# ESP32_USB_C.net
KiCad netlist of a schematic drawn in Altium Designer
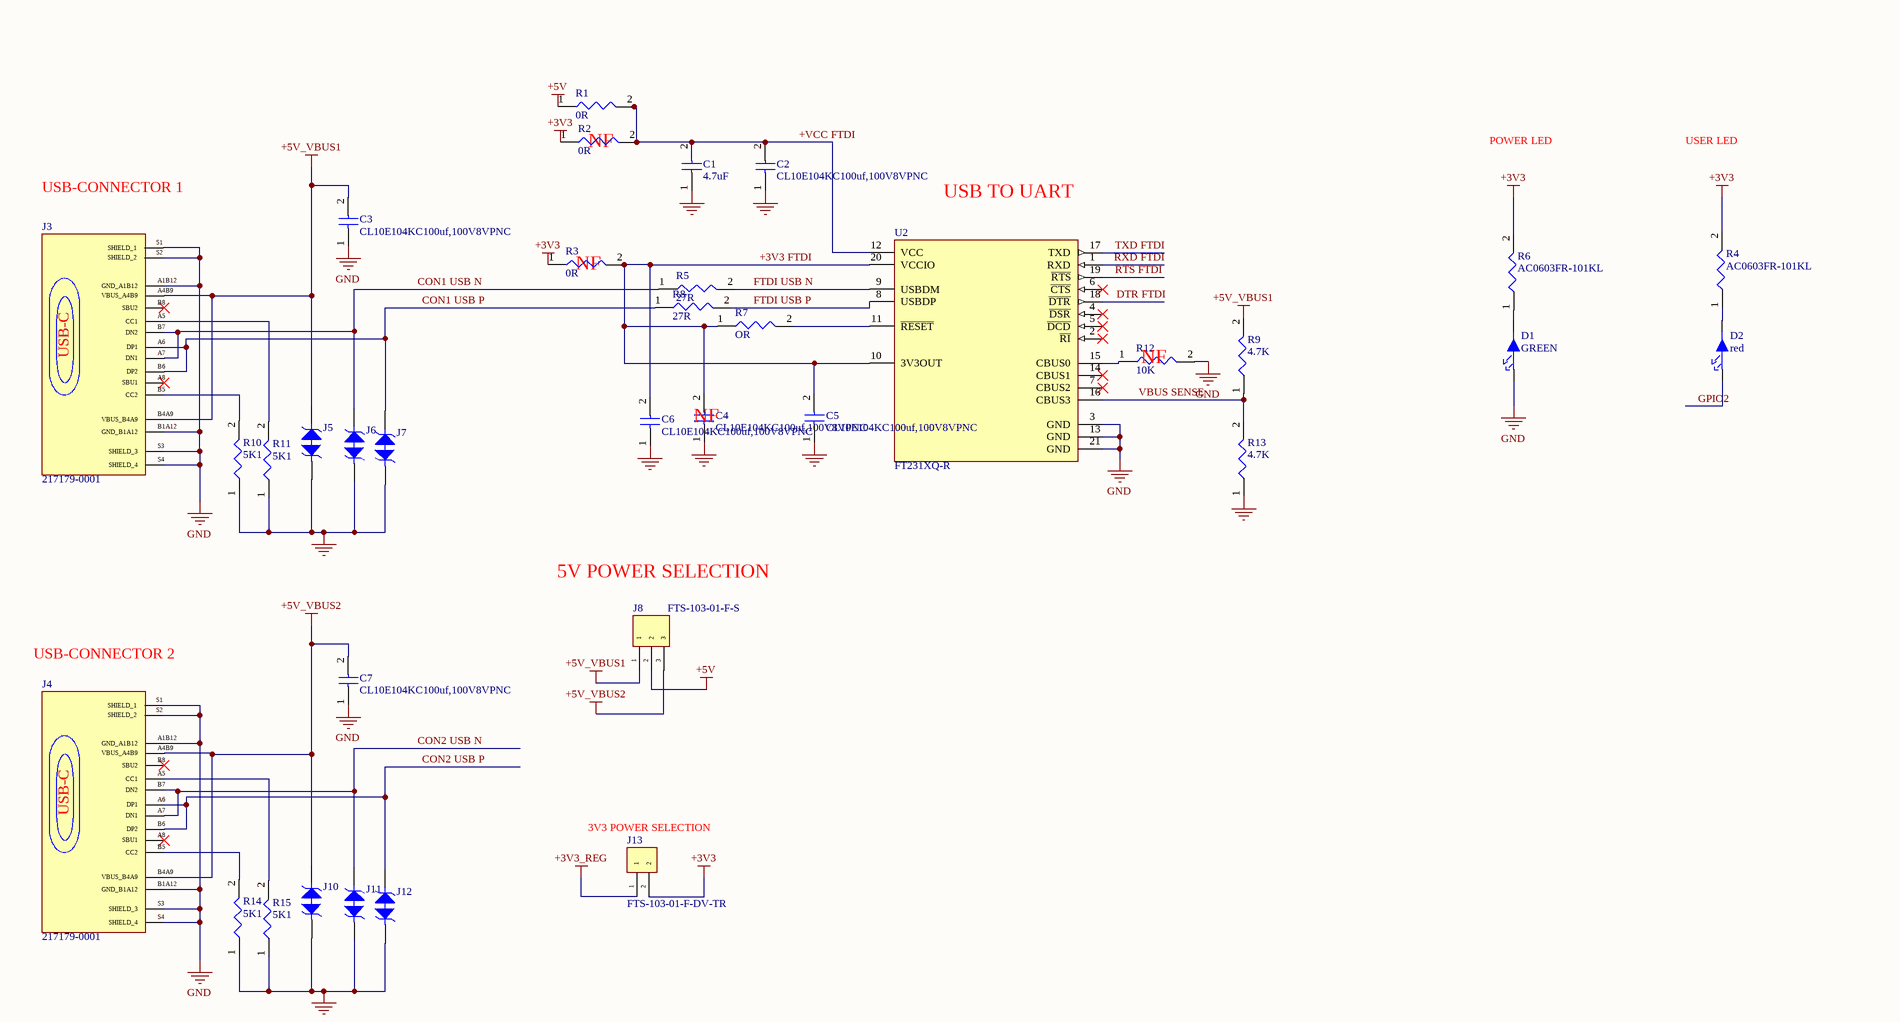
[diagram p0: ESP32_USB_C.SchDoc, top left]
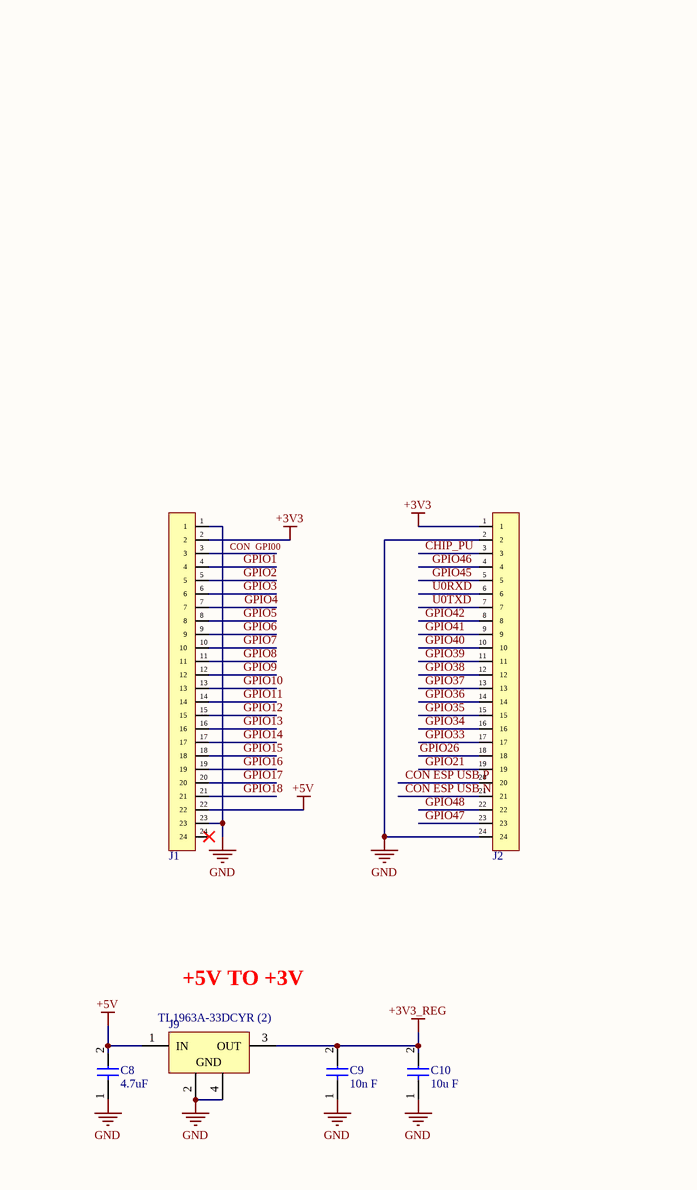
[diagram p1: ESP32_USB_C.SchDoc, top right]
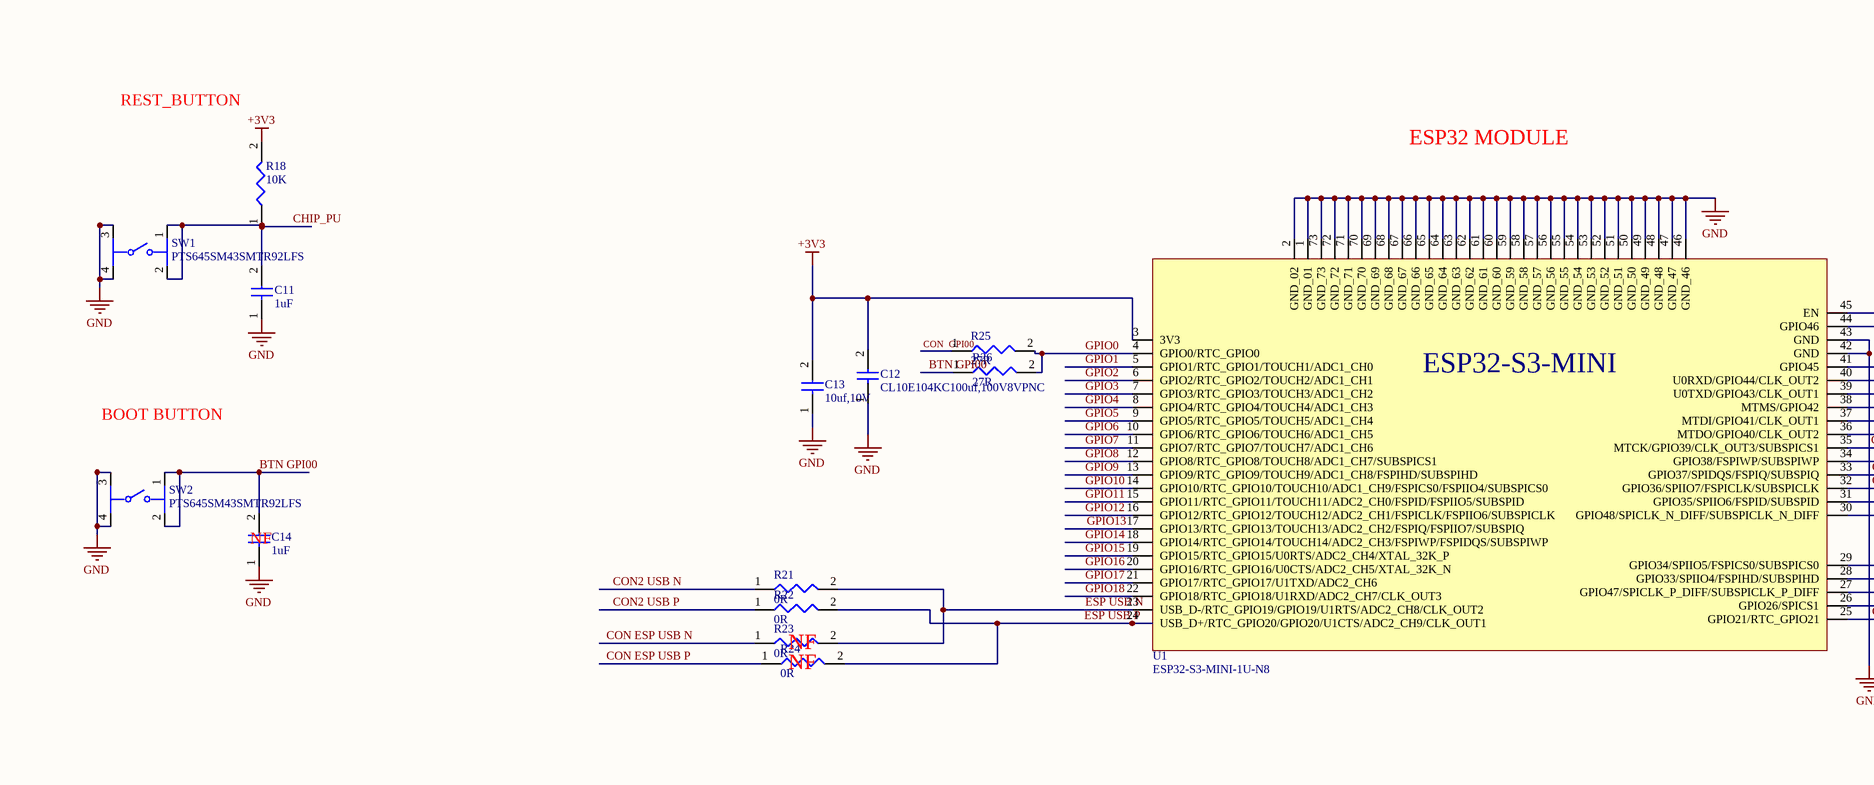
[diagram p2: ESP32_USB_C.SchDoc, bottom left]
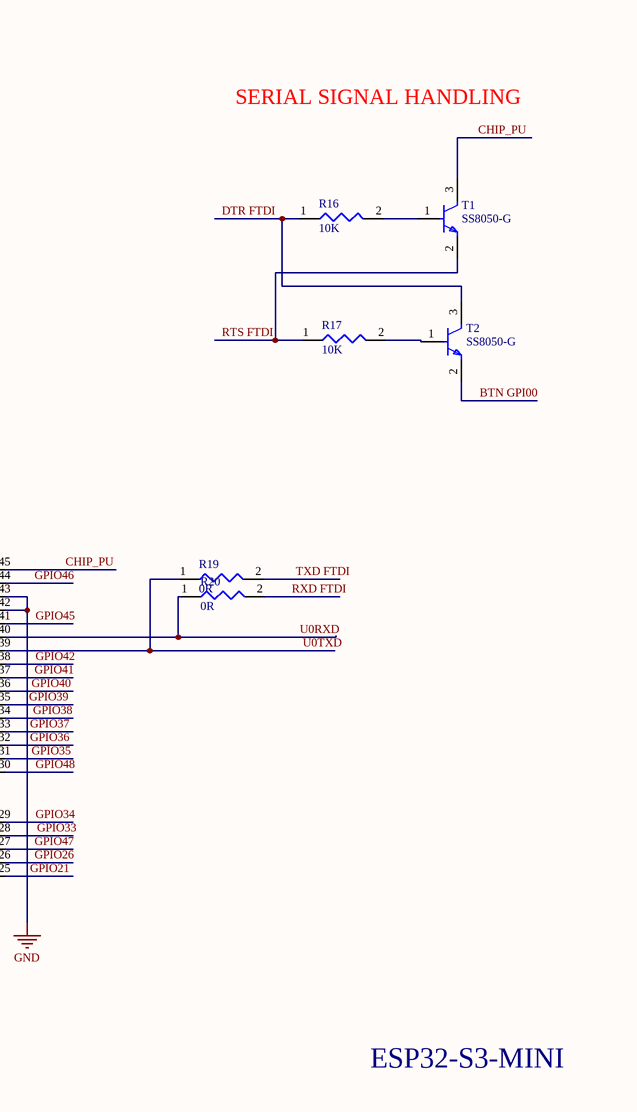
[diagram p3: ESP32_USB_C.SchDoc, bottom right]

(export (version "E")
  (design (tool "Eeschema 10.0.6"))
  (components
    (comp (ref "C1")
      (value "4.7uF")
      (footprint "CAPC1005X55N")
      (description "10V 4.7uF X5R ±20% 0402 Multilayer Ceramic Capacitors MLCC - SMD/SMT ROHS")
      (fields
        (field (name "MANUFACTURER") "Yageo Group")
        (field (name "MANUFACTURER PART NUMBER") "CC0402MRX5R6BB475")
      )
      (libsource (lib "ESP32_USB_C") (part "CC0402MRX5R6BB475"))
    )
    (comp (ref "C2")
      (value "CL10E104KC100uf,100V8VPNC")
      (footprint "CAPC1005X55N")
      (fields
        (field (name "MANUFACTURER") "Samsung Electro-Mechanics")
        (field (name "MANUFACTURER PART NUMBER") "CL10E104KC8VPNC")
      )
      (libsource (lib "ESP32_USB_C") (part "CL10E104KC8VPNC"))
    )
    (comp (ref "C3")
      (value "CL10E104KC100uf,100V8VPNC")
      (footprint "CAPC1005X55N")
      (fields
        (field (name "MANUFACTURER") "Samsung Electro-Mechanics")
        (field (name "MANUFACTURER PART NUMBER") "CL10E104KC8VPNC")
      )
      (libsource (lib "ESP32_USB_C") (part "CL10E104KC8VPNC"))
    )
    (comp (ref "C4")
      (value "CL10E104KC100uf,100V8VPNC")
      (footprint "CAPC1005X55N")
      (fields
        (field (name "MANUFACTURER") "Samsung Electro-Mechanics")
        (field (name "MANUFACTURER PART NUMBER") "CL10E104KC8VPNC")
      )
      (libsource (lib "ESP32_USB_C") (part "CL10E104KC8VPNC"))
    )
    (comp (ref "C5")
      (value "CL10E104KC100uf,100V8VPNC")
      (footprint "CAPC1005X55N")
      (fields
        (field (name "MANUFACTURER") "Samsung Electro-Mechanics")
        (field (name "MANUFACTURER PART NUMBER") "CL10E104KC8VPNC")
      )
      (libsource (lib "ESP32_USB_C") (part "CL10E104KC8VPNC"))
    )
    (comp (ref "C6")
      (value "CL10E104KC100uf,100V8VPNC")
      (footprint "CAPC1005X55N")
      (fields
        (field (name "MANUFACTURER") "Samsung Electro-Mechanics")
        (field (name "MANUFACTURER PART NUMBER") "CL10E104KC8VPNC")
      )
      (libsource (lib "ESP32_USB_C") (part "CL10E104KC8VPNC"))
    )
    (comp (ref "C7")
      (value "CL10E104KC100uf,100V8VPNC")
      (footprint "CAPC1005X55N")
      (fields
        (field (name "MANUFACTURER") "Samsung Electro-Mechanics")
        (field (name "MANUFACTURER PART NUMBER") "CL10E104KC8VPNC")
      )
      (libsource (lib "ESP32_USB_C") (part "CL10E104KC8VPNC"))
    )
    (comp (ref "C8")
      (value "4.7uF")
      (footprint "CAPC1005X55N")
      (description "10V 4.7uF X5R ±20% 0402 Multilayer Ceramic Capacitors MLCC - SMD/SMT ROHS")
      (fields
        (field (name "MANUFACTURER") "Yageo Group")
        (field (name "MANUFACTURER PART NUMBER") "CC0402MRX5R6BB475")
      )
      (libsource (lib "ESP32_USB_C") (part "CC0402MRX5R6BB475"))
    )
    (comp (ref "C9")
      (value "10n F")
      (footprint "CAPC1005X55N")
      (description "Surface Mount Ceramic Multilayer Capacitor Automotive Grade 0.01uF 20% X7R 50V 0612 Paper T/R")
      (fields
        (field (name "MANUFACTURER") "Yageo Group")
        (field (name "MANUFACTURER PART NUMBER") "AC0612MRX7R9BB103")
      )
      (libsource (lib "ESP32_USB_C") (part "AC0612MRX7R9BB103"))
    )
    (comp (ref "C10")
      (value "10u F")
      (footprint "CAPC1005X55N")
      (description "SMD Comm X7R 0805 (2012Metric) Ceramic Capacitor 0.079Lx0.049W 2.00mmx1.25mm X7R ±10% 10muF")
      (fields
        (field (name "MANUFACTURER") "Yageo Group")
        (field (name "MANUFACTURER PART NUMBER") "C0805C106K9RACTU")
      )
      (libsource (lib "ESP32_USB_C") (part "C0805C106K9RACTU"))
    )
    (comp (ref "C11")
      (value "1uF")
      (footprint "CAPC1005X55N")
      (description "16V 1uF X5R 卤10% 0402 Multilayer Ceramic Capacitors MLCC - SMD/SMT ROHS")
      (fields
        (field (name "MANUFACTURER") "Samsung Electro-Mechanics")
        (field (name "MANUFACTURER PART NUMBER") "CL05A105KO5NNNC")
      )
      (libsource (lib "ESP32_USB_C") (part "CL05A105KO5NNNC"))
    )
    (comp (ref "C12")
      (value "CL10E104KC100uf,100V8VPNC")
      (footprint "CAPC1005X55N")
      (fields
        (field (name "MANUFACTURER") "Samsung Electro-Mechanics")
        (field (name "MANUFACTURER PART NUMBER") "CL10E104KC8VPNC")
      )
      (libsource (lib "ESP32_USB_C") (part "CL10E104KC8VPNC"))
    )
    (comp (ref "C13")
      (value "10uf,10V")
      (footprint "CAPC1005X55N")
      (description "10V 10uF X5R 卤20% 0402 Multilayer Ceramic Capacitors MLCC - SMD/SMT ROHS")
      (fields
        (field (name "MANUFACTURER") "Samsung Electro-Mechanics")
        (field (name "MANUFACTURER PART NUMBER") "CL05A106MP8NUB8")
      )
      (libsource (lib "ESP32_USB_C") (part "CL05A106MP8NUB8"))
    )
    (comp (ref "C14")
      (value "1uF")
      (footprint "CAPC1005X55N")
      (description "16V 1uF X5R 卤10% 0402 Multilayer Ceramic Capacitors MLCC - SMD/SMT ROHS")
      (fields
        (field (name "MANUFACTURER") "Samsung Electro-Mechanics")
        (field (name "MANUFACTURER PART NUMBER") "CL05A105KO5NNNC")
      )
      (libsource (lib "ESP32_USB_C") (part "CL05A105KO5NNNC"))
    )
    (comp (ref "D1")
      (value "GREEN")
      (footprint "FP-APHCM2012CGCK-F01-MFG")
      (description "LED GREEN CLEAR CHIP SMD / Green 570nm LED Indication - Discrete 2.1V 0805 (2012 Metric)")
      (fields
        (field (name "MANUFACTURER") "Kingbright")
        (field (name "MANUFACTURER PART NUMBER") "APHCM2012CGCK-F01")
      )
      (libsource (lib "ESP32_USB_C") (part "APHCM2012CGCK-F01"))
    )
    (comp (ref "D2")
      (value "red")
      (footprint "LEDC2012X90N")
      (description "CML CMD17-21VRD/TR8 LED SMT 0805 2.0V 6mcd 140deg Red 3K Part of the VCC Family of Products")
      (fields (field (name "MANUFACTURER") "VCC") (field (name "MANUFACTURER PART NUMBER") "CMD17-21VRD/TR8"))
      (libsource (lib "ESP32_USB_C") (part "CMD17-21VRD/TR8"))
    )
    (comp (ref "J1")
      (value "22-28-4245")
      (footprint "7731111824LF")
      (description "Conn Unshrouded Header HDR 24 POS 2.54mm Solder ST Thru-Hole KK® Bag")
      (fields (field (name "MANUFACTURER") "Molex"))
      (libsource (lib "") (part "22-28-4245_1"))
    )
    (comp (ref "J2")
      (value "22-28-4245")
      (footprint "7731111824LF")
      (description "Conn Unshrouded Header HDR 24 POS 2.54mm Solder ST Thru-Hole KK® Bag")
      (fields (field (name "MANUFACTURER") "Molex"))
      (libsource (lib "ESP32_USB_C") (part "22-28-4245"))
    )
    (comp (ref "J3")
      (value "217179-0001")
      (footprint "FP-2171790001-MFG")
      (description "USB Connector, 16 Contact(s), Female, Right Angle, Surface Mount Terminal, Locking, Receptacle")
      (fields (field (name "MANUFACTURER") "Molex"))
      (libsource (lib "ESP32_USB_C") (part "217179-0001"))
    )
    (comp (ref "J4")
      (value "217179-0001")
      (footprint "FP-2171790001-MFG")
      (description "USB Connector, 16 Contact(s), Female, Right Angle, Surface Mount Terminal, Locking, Receptacle")
      (fields (field (name "MANUFACTURER") "Molex"))
      (libsource (lib "ESP32_USB_C") (part "217179-0001"))
    )
    (comp (ref "J5")
      (value "AQ3045-01ETG")
      (footprint "RTVS_SOD882_LTF-M")
      (description "TVS DIODE 12VC 3A SOD882 / ESD Suppressor TVS Bi-Dir 5.3V Automotive 2-Pin SOD-882 T/R")
      (fields (field (name "MANUFACTURER") "Littelfuse"))
      (libsource (lib "ESP32_USB_C") (part "AQ3045-01ETG"))
    )
    (comp (ref "J6")
      (value "AQ3045-01ETG")
      (footprint "RTVS_SOD882_LTF-M")
      (description "TVS DIODE 12VC 3A SOD882 / ESD Suppressor TVS Bi-Dir 5.3V Automotive 2-Pin SOD-882 T/R")
      (fields (field (name "MANUFACTURER") "Littelfuse"))
      (libsource (lib "ESP32_USB_C") (part "AQ3045-01ETG"))
    )
    (comp (ref "J7")
      (value "AQ3045-01ETG")
      (footprint "RTVS_SOD882_LTF-M")
      (description "TVS DIODE 12VC 3A SOD882 / ESD Suppressor TVS Bi-Dir 5.3V Automotive 2-Pin SOD-882 T/R")
      (fields (field (name "MANUFACTURER") "Littelfuse"))
      (libsource (lib "ESP32_USB_C") (part "AQ3045-01ETG"))
    )
    (comp (ref "J8")
      (value "FTS-103-01-F-S")
      (footprint "SAMTEC-FTS-103-01-X-S")
      (description "Pin Header, Board-to-Board, Wire-to-Board, 3.4 A, 1.27 mm, 1 Rows, 3 Contacts, Through Hole")
      (fields (field (name "MANUFACTURER") "Samtec"))
      (libsource (lib "ESP32_USB_C") (part "FTS-103-01-F-S"))
    )
    (comp (ref "J9")
      (value "TL1963A-33DCYR (2)")
      (footprint "DCY0004A_M")
      (description "1.5-A, 20-V, low-dropout voltage regulator with reverse current & reverse voltage protection")
      (fields
        (field (name "MANUFACTURER") "Texas Instruments")
        (field (name "MANUFACTURER PART NUMBER") "TL1963A-33DCYR")
      )
      (libsource (lib "ESP32_USB_C") (part "TL1963A-33DCYR (2)"))
    )
    (comp (ref "J10")
      (value "AQ3045-01ETG")
      (footprint "RTVS_SOD882_LTF-M")
      (description "TVS DIODE 12VC 3A SOD882 / ESD Suppressor TVS Bi-Dir 5.3V Automotive 2-Pin SOD-882 T/R")
      (fields (field (name "MANUFACTURER") "Littelfuse"))
      (libsource (lib "ESP32_USB_C") (part "AQ3045-01ETG"))
    )
    (comp (ref "J11")
      (value "AQ3045-01ETG")
      (footprint "RTVS_SOD882_LTF-M")
      (description "TVS DIODE 12VC 3A SOD882 / ESD Suppressor TVS Bi-Dir 5.3V Automotive 2-Pin SOD-882 T/R")
      (fields (field (name "MANUFACTURER") "Littelfuse"))
      (libsource (lib "ESP32_USB_C") (part "AQ3045-01ETG"))
    )
    (comp (ref "J12")
      (value "AQ3045-01ETG")
      (footprint "RTVS_SOD882_LTF-M")
      (description "TVS DIODE 12VC 3A SOD882 / ESD Suppressor TVS Bi-Dir 5.3V Automotive 2-Pin SOD-882 T/R")
      (fields (field (name "MANUFACTURER") "Littelfuse"))
      (libsource (lib "ESP32_USB_C") (part "AQ3045-01ETG"))
    )
    (comp (ref "J13")
      (value "FTS-103-01-F-DV-TR")
      (footprint "HDRV2W40P0X127_1X2_254X214X400P")
      (description "Pin Header, Board-to-Board, Wire-to-Board, 3.4 A, 1.27 mm, 2 Rows, 6 Contacts, Surface Mount")
      (fields (field (name "MANUFACTURER") "Samtec"))
      (libsource (lib "ESP32_USB_C") (part "FTS-103-01-F-DV-TR"))
    )
    (comp (ref "R1")
      (value "0R")
      (footprint "RESC1005X40N")
      (description "GENERAL PURPOSE CHIP RESISTOR Metal Glaze/thick Film, 0.0625W, 0ohm, Surface Mount, 0402")
      (fields
        (field (name "MANUFACTURER") "Yageo Group")
        (field (name "MANUFACTURER PART NUMBER") "RC0402JR-070RL")
      )
      (libsource (lib "ESP32_USB_C") (part "RC0402JR-070RL"))
    )
    (comp (ref "R2")
      (value "0R")
      (footprint "RESC1005X40N")
      (description "GENERAL PURPOSE CHIP RESISTOR Metal Glaze/thick Film, 0.0625W, 0ohm, Surface Mount, 0402")
      (fields
        (field (name "MANUFACTURER") "Yageo Group")
        (field (name "MANUFACTURER PART NUMBER") "RC0402JR-070RL")
      )
      (libsource (lib "ESP32_USB_C") (part "RC0402JR-070RL"))
    )
    (comp (ref "R3")
      (value "0R")
      (footprint "RESC1005X40N")
      (description "GENERAL PURPOSE CHIP RESISTOR Metal Glaze/thick Film, 0.0625W, 0ohm, Surface Mount, 0402")
      (fields
        (field (name "MANUFACTURER") "Yageo Group")
        (field (name "MANUFACTURER PART NUMBER") "RC0402JR-070RL")
      )
      (libsource (lib "ESP32_USB_C") (part "RC0402JR-070RL"))
    )
    (comp (ref "R4")
      (value "AC0603FR-101KL")
      (footprint "RESC1005X40N")
      (fields (field (name "MANUFACTURER") "Yageo Group") (field (name "TOLERANCE") "1%"))
      (libsource (lib "ESP32_USB_C") (part "AC0603FR-101KL"))
    )
    (comp (ref "R5")
      (value "27R")
      (footprint "RESC1005X40N")
      (description "62.5mW Thick Film Resistors 50V ±100ppm/℃ ±1% 27Ω 0402 Chip Resistor - Surface Mount ROHS")
      (fields
        (field (name "MANUFACTURER") "Yageo Group")
        (field (name "MANUFACTURER PART NUMBER") "RC0402FR-0727RL")
      )
      (libsource (lib "ESP32_USB_C") (part "RC0402FR-0727RL"))
    )
    (comp (ref "R6")
      (value "AC0603FR-101KL")
      (footprint "RESC1005X40N")
      (fields (field (name "MANUFACTURER") "Yageo Group") (field (name "TOLERANCE") "1%"))
      (libsource (lib "ESP32_USB_C") (part "AC0603FR-101KL"))
    )
    (comp (ref "R7")
      (value "OR")
      (footprint "RESC1005X40N")
      (description "Fixed Resistor, Thin Film, 0.063W, 1000ohm, 50V, 1% +/-Tol, 50ppm/Cel, Surface Mount, 0603")
      (fields
        (field (name "MANUFACTURER") "TE Connectivity")
        (field (name "MANUFACTURER PART NUMBER") "6-1879336-2")
      )
      (libsource (lib "ESP32_USB_C") (part "6-1879336-2"))
    )
    (comp (ref "R8")
      (value "27R")
      (footprint "RESC1005X40N")
      (description "62.5mW Thick Film Resistors 50V ±100ppm/℃ ±1% 27Ω 0402 Chip Resistor - Surface Mount ROHS")
      (fields
        (field (name "MANUFACTURER") "Yageo Group")
        (field (name "MANUFACTURER PART NUMBER") "RC0402FR-0727RL")
      )
      (libsource (lib "ESP32_USB_C") (part "RC0402FR-0727RL"))
    )
    (comp (ref "R9")
      (value "4.7K")
      (footprint "RESC1005X40N")
      (description "Res Thick Film 2512 4.7K Ohm 1% 1W ±100ppm/C Pad SMD T/R Automotive AEC-Q200")
      (fields
        (field (name "MANUFACTURER") "TE Connectivity")
        (field (name "MANUFACTURER PART NUMBER") "CRGCQ2512F4K7")
      )
      (libsource (lib "ESP32_USB_C") (part "CRGCQ2512F4K7"))
    )
    (comp (ref "R10")
      (value "5K1")
      (footprint "RESC1005X40N")
      (description "Res Thick Film 0402 5.1K Ohm 1% 0.1W(1/10W) ±100ppm/C Pad SMD Automotive T/R")
      (fields
        (field (name "MANUFACTURER") "Panasonic")
        (field (name "MANUFACTURER PART NUMBER") "ERJ2RKF5101X")
      )
      (libsource (lib "ESP32_USB_C") (part "ERJ2RKF5101X"))
    )
    (comp (ref "R11")
      (value "5K1")
      (footprint "RESC1005X40N")
      (description "Res Thick Film 0402 5.1K Ohm 1% 0.1W(1/10W) ±100ppm/C Pad SMD Automotive T/R")
      (fields
        (field (name "MANUFACTURER") "Panasonic")
        (field (name "MANUFACTURER PART NUMBER") "ERJ2RKF5101X")
      )
      (libsource (lib "ESP32_USB_C") (part "ERJ2RKF5101X"))
    )
    (comp (ref "R12")
      (value "10K")
      (footprint "RESC1005X40N")
      (description "Fixed Resistor, Metal Glaze/Thick Film, 0.2W, 10000ohm, 75V, 1% +/-Tol, Surface Mount, 0603")
      (fields
        (field (name "MANUFACTURER") "Yageo Group")
        (field (name "MANUFACTURER PART NUMBER") "AC0603FR-7W10KL")
      )
      (libsource (lib "ESP32_USB_C") (part "AC0603FR-7W10KL"))
    )
    (comp (ref "R13")
      (value "4.7K")
      (footprint "RESC1005X40N")
      (description "Res Thick Film 2512 4.7K Ohm 1% 1W ±100ppm/C Pad SMD T/R Automotive AEC-Q200")
      (fields
        (field (name "MANUFACTURER") "TE Connectivity")
        (field (name "MANUFACTURER PART NUMBER") "CRGCQ2512F4K7")
      )
      (libsource (lib "ESP32_USB_C") (part "CRGCQ2512F4K7"))
    )
    (comp (ref "R14")
      (value "5K1")
      (footprint "RESC1005X40N")
      (description "Res Thick Film 0402 5.1K Ohm 1% 0.1W(1/10W) ±100ppm/C Pad SMD Automotive T/R")
      (fields
        (field (name "MANUFACTURER") "Panasonic")
        (field (name "MANUFACTURER PART NUMBER") "ERJ2RKF5101X")
      )
      (libsource (lib "ESP32_USB_C") (part "ERJ2RKF5101X"))
    )
    (comp (ref "R15")
      (value "5K1")
      (footprint "RESC1005X40N")
      (description "Res Thick Film 0402 5.1K Ohm 1% 0.1W(1/10W) ±100ppm/C Pad SMD Automotive T/R")
      (fields
        (field (name "MANUFACTURER") "Panasonic")
        (field (name "MANUFACTURER PART NUMBER") "ERJ2RKF5101X")
      )
      (libsource (lib "ESP32_USB_C") (part "ERJ2RKF5101X"))
    )
    (comp (ref "R16")
      (value "10K")
      (footprint "RESC1005X40N")
      (description "Fixed Resistor, Metal Glaze/Thick Film, 0.2W, 10000ohm, 75V, 1% +/-Tol, Surface Mount, 0603")
      (fields
        (field (name "MANUFACTURER") "Yageo Group")
        (field (name "MANUFACTURER PART NUMBER") "AC0603FR-7W10KL")
      )
      (libsource (lib "ESP32_USB_C") (part "AC0603FR-7W10KL"))
    )
    (comp (ref "R17")
      (value "10K")
      (footprint "RESC1005X40N")
      (description "Fixed Resistor, Metal Glaze/Thick Film, 0.2W, 10000ohm, 75V, 1% +/-Tol, Surface Mount, 0603")
      (fields
        (field (name "MANUFACTURER") "Yageo Group")
        (field (name "MANUFACTURER PART NUMBER") "AC0603FR-7W10KL")
      )
      (libsource (lib "ESP32_USB_C") (part "AC0603FR-7W10KL"))
    )
    (comp (ref "R18")
      (value "10K")
      (footprint "RESC1005X40N")
      (description "Res Thick Film 0402 10K Ohm 1% 0.063W(1/16W) ±100ppm/°C Pad SMD T/R")
      (fields
        (field (name "MANUFACTURER") "Samsung Electro-Mechanics")
        (field (name "MANUFACTURER PART NUMBER") "RC1005F103CS")
      )
      (libsource (lib "ESP32_USB_C") (part "RC1005F103CS"))
    )
    (comp (ref "R19")
      (value "0R")
      (footprint "RESC1005X40N")
      (description "GENERAL PURPOSE CHIP RESISTOR Metal Glaze/thick Film, 0.0625W, 0ohm, Surface Mount, 0402")
      (fields
        (field (name "MANUFACTURER") "Yageo Group")
        (field (name "MANUFACTURER PART NUMBER") "RC0402JR-070RL")
      )
      (libsource (lib "ESP32_USB_C") (part "RC0402JR-070RL"))
    )
    (comp (ref "R20")
      (value "0R")
      (footprint "RESC1005X40N")
      (description "GENERAL PURPOSE CHIP RESISTOR Metal Glaze/thick Film, 0.0625W, 0ohm, Surface Mount, 0402")
      (fields
        (field (name "MANUFACTURER") "Yageo Group")
        (field (name "MANUFACTURER PART NUMBER") "RC0402JR-070RL")
      )
      (libsource (lib "ESP32_USB_C") (part "RC0402JR-070RL"))
    )
    (comp (ref "R21")
      (value "0R")
      (footprint "RESC1005X40N")
      (description "GENERAL PURPOSE CHIP RESISTOR Metal Glaze/thick Film, 0.0625W, 0ohm, Surface Mount, 0402")
      (fields
        (field (name "MANUFACTURER") "Yageo Group")
        (field (name "MANUFACTURER PART NUMBER") "RC0402JR-070RL")
      )
      (libsource (lib "ESP32_USB_C") (part "RC0402JR-070RL"))
    )
    (comp (ref "R22")
      (value "0R")
      (footprint "RESC1005X40N")
      (description "GENERAL PURPOSE CHIP RESISTOR Metal Glaze/thick Film, 0.0625W, 0ohm, Surface Mount, 0402")
      (fields
        (field (name "MANUFACTURER") "Yageo Group")
        (field (name "MANUFACTURER PART NUMBER") "RC0402JR-070RL")
      )
      (libsource (lib "ESP32_USB_C") (part "RC0402JR-070RL"))
    )
    (comp (ref "R23")
      (value "0R")
      (footprint "RESC1005X40N")
      (description "GENERAL PURPOSE CHIP RESISTOR Metal Glaze/thick Film, 0.0625W, 0ohm, Surface Mount, 0402")
      (fields
        (field (name "MANUFACTURER") "Yageo Group")
        (field (name "MANUFACTURER PART NUMBER") "RC0402JR-070RL")
      )
      (libsource (lib "ESP32_USB_C") (part "RC0402JR-070RL"))
    )
    (comp (ref "R24")
      (value "0R")
      (footprint "RESC1005X40N")
      (description "GENERAL PURPOSE CHIP RESISTOR Metal Glaze/thick Film, 0.0625W, 0ohm, Surface Mount, 0402")
      (fields
        (field (name "MANUFACTURER") "Yageo Group")
        (field (name "MANUFACTURER PART NUMBER") "RC0402JR-070RL")
      )
      (libsource (lib "ESP32_USB_C") (part "RC0402JR-070RL"))
    )
    (comp (ref "R25")
      (value "27R")
      (footprint "RESC1005X40N")
      (description "62.5mW Thick Film Resistors 50V ±100ppm/℃ ±1% 27Ω 0402 Chip Resistor - Surface Mount ROHS")
      (fields
        (field (name "MANUFACTURER") "Yageo Group")
        (field (name "MANUFACTURER PART NUMBER") "RC0402FR-0727RL")
      )
      (libsource (lib "ESP32_USB_C") (part "RC0402FR-0727RL"))
    )
    (comp (ref "R26")
      (value "27R")
      (footprint "RESC1005X40N")
      (description "62.5mW Thick Film Resistors 50V ±100ppm/℃ ±1% 27Ω 0402 Chip Resistor - Surface Mount ROHS")
      (fields
        (field (name "MANUFACTURER") "Yageo Group")
        (field (name "MANUFACTURER PART NUMBER") "RC0402FR-0727RL")
      )
      (libsource (lib "ESP32_USB_C") (part "RC0402FR-0727RL"))
    )
    (comp (ref "SW1")
      (value "PTS645SM43SMTR92LFS")
      (footprint "PTS645SM43SMTR92LFS_MFG")
      (description "Switch Tactile N.O SPST Round Button Gull Wing 0.05A 12VDC 100000Cycle 1.57N SMD T/R")
      (fields (field (name "MANUFACTURER") "C&K Components"))
      (libsource (lib "ESP32_USB_C") (part "PTS645SM43SMTR92LFS"))
    )
    (comp (ref "SW2")
      (value "PTS645SM43SMTR92LFS")
      (footprint "PTS645SM43SMTR92LFS_MFG")
      (description "Switch Tactile N.O SPST Round Button Gull Wing 0.05A 12VDC 100000Cycle 1.57N SMD T/R")
      (fields (field (name "MANUFACTURER") "C&K Components"))
      (libsource (lib "ESP32_USB_C") (part "PTS645SM43SMTR92LFS"))
    )
    (comp (ref "T1")
      (value "SS8050-G")
      (footprint "FP-SS8050-G-IPC_B")
      (fields (field (name "MANUFACTURER") "Comchip"))
      (libsource (lib "ESP32_USB_C") (part "SS8050-G"))
    )
    (comp (ref "T2")
      (value "SS8050-G")
      (footprint "FP-SS8050-G-IPC_B")
      (fields (field (name "MANUFACTURER") "Comchip"))
      (libsource (lib "ESP32_USB_C") (part "SS8050-G"))
    )
    (comp (ref "U1")
      (value "ESP32-S3-MINI-1U-N8")
      (footprint "XCVR_ESP32-S3-MINI-1U-N8")
      (description "WiFi-Module 802.11 2, 4GHz 150Mb/s")
      (fields (field (name "MANUFACTURER") "Espressif Systems"))
      (libsource (lib "ESP32_USB_C") (part "ESP32-S3-MINI-1U-N8"))
    )
    (comp (ref "U2")
      (value "FT231XQ-R")
      (footprint "FP-QFN-20-IPC_B")
      (libsource (lib "ESP32_USB_C") (part "FT231XQ-R Tape & Reel (TR) 2006 UART USB 2.0 interface controller 3.3V~5V 4mm 8mA 12Mbps UART Interface ICs Tape & Reel (TR) 2006 UART USB 2.0 interface controller 3.3V~5V 4mm 8mA 12Mbps"))
    )
  )
  (nets
    (net (code "1") (name "+3V3") (class "Default")
      (node (ref "C12") (pin "2") (pinfunction "2_2") (pintype "passive"))
      (node (ref "C13") (pin "2") (pinfunction "2_2") (pintype "passive"))
      (node (ref "J1") (pin "2") (pinfunction "2_2") (pintype "passive"))
      (node (ref "J13") (pin "2") (pinfunction "2_2") (pintype "passive"))
      (node (ref "J2") (pin "1") (pinfunction "1_1") (pintype "passive"))
      (node (ref "R18") (pin "2") (pinfunction "2_2") (pintype "passive"))
      (node (ref "R2") (pin "1") (pinfunction "1_1") (pintype "passive"))
      (node (ref "R3") (pin "1") (pinfunction "1_1") (pintype "passive"))
      (node (ref "R4") (pin "2") (pinfunction "2_2") (pintype "passive"))
      (node (ref "R6") (pin "2") (pinfunction "2_2") (pintype "passive"))
      (node (ref "U1") (pin "3") (pinfunction "3V3_3") (pintype "passive"))
    )
    (net (code "2") (name "+3V3_REG") (class "Default")
      (node (ref "C10") (pin "2") (pinfunction "2_2") (pintype "passive"))
      (node (ref "C9") (pin "2") (pinfunction "2_2") (pintype "passive"))
      (node (ref "J13") (pin "1") (pinfunction "1_1") (pintype "passive"))
      (node (ref "J9") (pin "3") (pinfunction "OUT_3") (pintype "power_in"))
    )
    (net (code "3") (name "+5V") (class "Default")
      (node (ref "C8") (pin "2") (pinfunction "2_2") (pintype "passive"))
      (node (ref "J1") (pin "22") (pinfunction "22_22") (pintype "passive"))
      (node (ref "J8") (pin "2") (pinfunction "2_2") (pintype "passive"))
      (node (ref "J9") (pin "1") (pinfunction "IN_1") (pintype "power_in"))
      (node (ref "R1") (pin "1") (pinfunction "1_1") (pintype "passive"))
    )
    (net (code "4") (name "+5V_VBUS1") (class "Default")
      (node (ref "C3") (pin "2") (pinfunction "2_2") (pintype "passive"))
      (node (ref "J3") (pin "A4B9") (pinfunction "VBUS_A4B9_A4B9") (pintype "passive"))
      (node (ref "J3") (pin "B4A9") (pinfunction "VBUS_B4A9_B4A9") (pintype "passive"))
      (node (ref "J5") (pin "2") (pintype "passive"))
      (node (ref "J8") (pin "1") (pinfunction "1_1") (pintype "passive"))
      (node (ref "R9") (pin "2") (pinfunction "2_2") (pintype "passive"))
    )
    (net (code "5") (name "+5V_VBUS2") (class "Default")
      (node (ref "C7") (pin "2") (pinfunction "2_2") (pintype "passive"))
      (node (ref "J10") (pin "2") (pintype "passive"))
      (node (ref "J4") (pin "A4B9") (pinfunction "VBUS_A4B9_A4B9") (pintype "passive"))
      (node (ref "J4") (pin "B4A9") (pinfunction "VBUS_B4A9_B4A9") (pintype "passive"))
      (node (ref "J8") (pin "3") (pinfunction "3_3") (pintype "passive"))
    )
    (net (code "6") (name "/+3V3 FTDI") (class "Default")
      (node (ref "C4") (pin "2") (pinfunction "2_2") (pintype "passive"))
      (node (ref "C5") (pin "2") (pinfunction "2_2") (pintype "passive"))
      (node (ref "C6") (pin "2") (pinfunction "2_2") (pintype "passive"))
      (node (ref "R3") (pin "2") (pinfunction "2_2") (pintype "passive"))
      (node (ref "R7") (pin "1") (pinfunction "1_1") (pintype "passive"))
      (node (ref "U2") (pin "10") (pinfunction "3V3OUT_10") (pintype "passive"))
      (node (ref "U2") (pin "20") (pinfunction "VCCIO_20") (pintype "passive"))
    )
    (net (code "7") (name "/+VCC FTDI") (class "Default")
      (node (ref "C1") (pin "2") (pinfunction "2_2") (pintype "passive"))
      (node (ref "C2") (pin "2") (pinfunction "2_2") (pintype "passive"))
      (node (ref "R1") (pin "2") (pinfunction "2_2") (pintype "passive"))
      (node (ref "R2") (pin "2") (pinfunction "2_2") (pintype "passive"))
      (node (ref "U2") (pin "12") (pinfunction "VCC_12") (pintype "passive"))
    )
    (net (code "8") (name "/BTN GPI00") (class "Default")
      (node (ref "C14") (pin "2") (pinfunction "2_2") (pintype "passive"))
      (node (ref "R26") (pin "1") (pinfunction "1_1") (pintype "passive"))
      (node (ref "SW2") (pin "1") (pinfunction "1_1") (pintype "passive"))
      (node (ref "SW2") (pin "2") (pinfunction "2_2") (pintype "passive"))
      (node (ref "T2") (pin "2") (pinfunction "E_2") (pintype "passive"))
    )
    (net (code "9") (name "/CHIP_PU") (class "Default")
      (node (ref "C11") (pin "2") (pinfunction "2_2") (pintype "passive"))
      (node (ref "J2") (pin "3") (pinfunction "3_3") (pintype "passive"))
      (node (ref "R18") (pin "1") (pinfunction "1_1") (pintype "passive"))
      (node (ref "SW1") (pin "1") (pinfunction "1_1") (pintype "passive"))
      (node (ref "SW1") (pin "2") (pinfunction "2_2") (pintype "passive"))
      (node (ref "T1") (pin "3") (pinfunction "C_3") (pintype "passive"))
      (node (ref "U1") (pin "45") (pinfunction "EN_45") (pintype "passive"))
    )
    (net (code "10") (name "/CON  GPI00") (class "Default")
      (node (ref "J1") (pin "3") (pinfunction "3_3") (pintype "passive"))
      (node (ref "R25") (pin "1") (pinfunction "1_1") (pintype "passive"))
    )
    (net (code "11") (name "/CON ESP USB N") (class "Default")
      (node (ref "J2") (pin "21") (pinfunction "21_21") (pintype "passive"))
      (node (ref "R23") (pin "1") (pinfunction "1_1") (pintype "passive"))
    )
    (net (code "12") (name "/CON ESP USB P") (class "Default")
      (node (ref "J2") (pin "20") (pinfunction "20_20") (pintype "passive"))
      (node (ref "R24") (pin "1") (pinfunction "1_1") (pintype "passive"))
    )
    (net (code "13") (name "/CON1 USB N") (class "Default")
      (node (ref "J3") (pin "A7") (pinfunction "DN1_A7") (pintype "passive"))
      (node (ref "J3") (pin "B7") (pinfunction "DN2_B7") (pintype "passive"))
      (node (ref "J6") (pin "2") (pintype "passive"))
      (node (ref "R5") (pin "1") (pinfunction "1_1") (pintype "passive"))
    )
    (net (code "14") (name "/CON1 USB P") (class "Default")
      (node (ref "J3") (pin "A6") (pinfunction "DP1_A6") (pintype "passive"))
      (node (ref "J3") (pin "B6") (pinfunction "DP2_B6") (pintype "passive"))
      (node (ref "J7") (pin "2") (pintype "passive"))
      (node (ref "R8") (pin "1") (pinfunction "1_1") (pintype "passive"))
    )
    (net (code "15") (name "/CON2 USB N") (class "Default")
      (node (ref "J11") (pin "2") (pintype "passive"))
      (node (ref "J4") (pin "A7") (pinfunction "DN1_A7") (pintype "passive"))
      (node (ref "J4") (pin "B7") (pinfunction "DN2_B7") (pintype "passive"))
      (node (ref "R21") (pin "1") (pinfunction "1_1") (pintype "passive"))
    )
    (net (code "16") (name "/CON2 USB P") (class "Default")
      (node (ref "J12") (pin "2") (pintype "passive"))
      (node (ref "J4") (pin "A6") (pinfunction "DP1_A6") (pintype "passive"))
      (node (ref "J4") (pin "B6") (pinfunction "DP2_B6") (pintype "passive"))
      (node (ref "R22") (pin "1") (pinfunction "1_1") (pintype "passive"))
    )
    (net (code "17") (name "/DTR FTDI") (class "Default")
      (node (ref "R16") (pin "1") (pinfunction "1_1") (pintype "passive"))
      (node (ref "T2") (pin "3") (pinfunction "C_3") (pintype "passive"))
      (node (ref "U2") (pin "18") (pinfunction "~{DTR}_18") (pintype "output"))
    )
    (net (code "18") (name "/ESP USB N") (class "Default")
      (node (ref "R21") (pin "2") (pinfunction "2_2") (pintype "passive"))
      (node (ref "R23") (pin "2") (pinfunction "2_2") (pintype "passive"))
      (node (ref "U1") (pin "23") (pinfunction "USB_D-/RTC_GPIO19/GPIO19/U1RTS/ADC2_CH8/CLK_OUT2_23") (pintype "passive"))
    )
    (net (code "19") (name "/ESP USB P") (class "Default")
      (node (ref "R22") (pin "2") (pinfunction "2_2") (pintype "passive"))
      (node (ref "R24") (pin "2") (pinfunction "2_2") (pintype "passive"))
      (node (ref "U1") (pin "24") (pinfunction "USB_D+/RTC_GPIO20/GPIO20/U1CTS/ADC2_CH9/CLK_OUT1_24") (pintype "passive"))
    )
    (net (code "20") (name "/FTDI USB N") (class "Default")
      (node (ref "R5") (pin "2") (pinfunction "2_2") (pintype "passive"))
      (node (ref "U2") (pin "9") (pinfunction "USBDM_9") (pintype "passive"))
    )
    (net (code "21") (name "/FTDI USB P") (class "Default")
      (node (ref "R8") (pin "2") (pinfunction "2_2") (pintype "passive"))
      (node (ref "U2") (pin "8") (pinfunction "USBDP_8") (pintype "passive"))
    )
    (net (code "22") (name "/GPIO0") (class "Default")
      (node (ref "R25") (pin "2") (pinfunction "2_2") (pintype "passive"))
      (node (ref "R26") (pin "2") (pinfunction "2_2") (pintype "passive"))
      (node (ref "U1") (pin "4") (pinfunction "GPIO0/RTC_GPIO0_4") (pintype "passive"))
    )
    (net (code "23") (name "/GPIO1") (class "Default")
      (node (ref "J1") (pin "4") (pinfunction "4_4") (pintype "passive"))
      (node (ref "U1") (pin "5") (pinfunction "GPIO1/RTC_GPIO1/TOUCH1/ADC1_CH0_5") (pintype "passive"))
    )
    (net (code "24") (name "/GPIO2") (class "Default")
      (node (ref "D2") (pin "1") (pinfunction "1_1") (pintype "passive"))
      (node (ref "J1") (pin "5") (pinfunction "5_5") (pintype "passive"))
      (node (ref "U1") (pin "6") (pinfunction "GPIO2/RTC_GPIO2/TOUCH2/ADC1_CH1_6") (pintype "passive"))
    )
    (net (code "25") (name "/GPIO3") (class "Default")
      (node (ref "J1") (pin "6") (pinfunction "6_6") (pintype "passive"))
      (node (ref "U1") (pin "7") (pinfunction "GPIO3/RTC_GPIO3/TOUCH3/ADC1_CH2_7") (pintype "passive"))
    )
    (net (code "26") (name "/GPIO4") (class "Default")
      (node (ref "J1") (pin "7") (pinfunction "7_7") (pintype "passive"))
      (node (ref "U1") (pin "8") (pinfunction "GPIO4/RTC_GPIO4/TOUCH4/ADC1_CH3_8") (pintype "passive"))
    )
    (net (code "27") (name "/GPIO5") (class "Default")
      (node (ref "J1") (pin "8") (pinfunction "8_8") (pintype "passive"))
      (node (ref "U1") (pin "9") (pinfunction "GPIO5/RTC_GPIO5/TOUCH5/ADC1_CH4_9") (pintype "passive"))
    )
    (net (code "28") (name "/GPIO6") (class "Default")
      (node (ref "J1") (pin "9") (pinfunction "9_9") (pintype "passive"))
      (node (ref "U1") (pin "10") (pinfunction "GPIO6/RTC_GPIO6/TOUCH6/ADC1_CH5_10") (pintype "passive"))
    )
    (net (code "29") (name "/GPIO7") (class "Default")
      (node (ref "J1") (pin "10") (pinfunction "10_10") (pintype "passive"))
      (node (ref "U1") (pin "11") (pinfunction "GPIO7/RTC_GPIO7/TOUCH7/ADC1_CH6_11") (pintype "passive"))
    )
    (net (code "30") (name "/GPIO8") (class "Default")
      (node (ref "J1") (pin "11") (pinfunction "11_11") (pintype "passive"))
      (node (ref "U1") (pin "12") (pinfunction "GPIO8/RTC_GPIO8/TOUCH8/ADC1_CH7/SUBSPICS1_12") (pintype "passive"))
    )
    (net (code "31") (name "/GPIO9") (class "Default")
      (node (ref "J1") (pin "12") (pinfunction "12_12") (pintype "passive"))
      (node (ref "U1") (pin "13") (pinfunction "GPIO9/RTC_GPIO9/TOUCH9/ADC1_CH8/FSPIHD/SUBSPIHD_13") (pintype "passive"))
    )
    (net (code "32") (name "/GPIO10") (class "Default")
      (node (ref "J1") (pin "13") (pinfunction "13_13") (pintype "passive"))
      (node (ref "U1") (pin "14") (pinfunction "GPIO10/RTC_GPIO10/TOUCH10/ADC1_CH9/FSPICS0/FSPIIO4/SUBSPICS0_14") (pintype "passive"))
    )
    (net (code "33") (name "/GPIO11") (class "Default")
      (node (ref "J1") (pin "14") (pinfunction "14_14") (pintype "passive"))
      (node (ref "U1") (pin "15") (pinfunction "GPIO11/RTC_GPIO11/TOUCH11/ADC2_CH0/FSPID/FSPIIO5/SUBSPID_15") (pintype "passive"))
    )
    (net (code "34") (name "/GPIO12") (class "Default")
      (node (ref "J1") (pin "15") (pinfunction "15_15") (pintype "passive"))
      (node (ref "U1") (pin "16") (pinfunction "GPIO12/RTC_GPIO12/TOUCH12/ADC2_CH1/FSPICLK/FSPIIO6/SUBSPICLK_16") (pintype "passive"))
    )
    (net (code "35") (name "/GPIO13") (class "Default")
      (node (ref "J1") (pin "16") (pinfunction "16_16") (pintype "passive"))
      (node (ref "U1") (pin "17") (pinfunction "GPIO13/RTC_GPIO13/TOUCH13/ADC2_CH2/FSPIQ/FSPIIO7/SUBSPIQ_17") (pintype "passive"))
    )
    (net (code "36") (name "/GPIO14") (class "Default")
      (node (ref "J1") (pin "17") (pinfunction "17_17") (pintype "passive"))
      (node (ref "U1") (pin "18") (pinfunction "GPIO14/RTC_GPIO14/TOUCH14/ADC2_CH3/FSPIWP/FSPIDQS/SUBSPIWP_18") (pintype "passive"))
    )
    (net (code "37") (name "/GPIO15") (class "Default")
      (node (ref "J1") (pin "18") (pinfunction "18_18") (pintype "passive"))
      (node (ref "U1") (pin "19") (pinfunction "GPIO15/RTC_GPIO15/U0RTS/ADC2_CH4/XTAL_32K_P_19") (pintype "passive"))
    )
    (net (code "38") (name "/GPIO16") (class "Default")
      (node (ref "J1") (pin "19") (pinfunction "19_19") (pintype "passive"))
      (node (ref "U1") (pin "20") (pinfunction "GPIO16/RTC_GPIO16/U0CTS/ADC2_CH5/XTAL_32K_N_20") (pintype "passive"))
    )
    (net (code "39") (name "/GPIO17") (class "Default")
      (node (ref "J1") (pin "20") (pinfunction "20_20") (pintype "passive"))
      (node (ref "U1") (pin "21") (pinfunction "GPIO17/RTC_GPIO17/U1TXD/ADC2_CH6_21") (pintype "passive"))
    )
    (net (code "40") (name "/GPIO18") (class "Default")
      (node (ref "J1") (pin "21") (pinfunction "21_21") (pintype "passive"))
      (node (ref "U1") (pin "22") (pinfunction "GPIO18/RTC_GPIO18/U1RXD/ADC2_CH7/CLK_OUT3_22") (pintype "passive"))
    )
    (net (code "41") (name "/GPIO21") (class "Default")
      (node (ref "J2") (pin "19") (pinfunction "19_19") (pintype "passive"))
      (node (ref "U1") (pin "25") (pinfunction "GPIO21/RTC_GPIO21_25") (pintype "passive"))
    )
    (net (code "42") (name "/GPIO26") (class "Default")
      (node (ref "J2") (pin "18") (pinfunction "18_18") (pintype "passive"))
      (node (ref "U1") (pin "26") (pinfunction "GPIO26/SPICS1_26") (pintype "passive"))
    )
    (net (code "43") (name "/GPIO33") (class "Default")
      (node (ref "J2") (pin "17") (pinfunction "17_17") (pintype "passive"))
      (node (ref "U1") (pin "28") (pinfunction "GPIO33/SPIIO4/FSPIHD/SUBSPIHD_28") (pintype "passive"))
    )
    (net (code "44") (name "/GPIO34") (class "Default")
      (node (ref "J2") (pin "16") (pinfunction "16_16") (pintype "passive"))
      (node (ref "U1") (pin "29") (pinfunction "GPIO34/SPIIO5/FSPICS0/SUBSPICS0_29") (pintype "passive"))
    )
    (net (code "45") (name "/GPIO35") (class "Default")
      (node (ref "J2") (pin "15") (pinfunction "15_15") (pintype "passive"))
      (node (ref "U1") (pin "31") (pinfunction "GPIO35/SPIIO6/FSPID/SUBSPID_31") (pintype "passive"))
    )
    (net (code "46") (name "/GPIO36") (class "Default")
      (node (ref "J2") (pin "14") (pinfunction "14_14") (pintype "passive"))
      (node (ref "U1") (pin "32") (pinfunction "GPIO36/SPIIO7/FSPICLK/SUBSPICLK_32") (pintype "passive"))
    )
    (net (code "47") (name "/GPIO37") (class "Default")
      (node (ref "J2") (pin "13") (pinfunction "13_13") (pintype "passive"))
      (node (ref "U1") (pin "33") (pinfunction "GPIO37/SPIDQS/FSPIQ/SUBSPIQ_33") (pintype "passive"))
    )
    (net (code "48") (name "/GPIO38") (class "Default")
      (node (ref "J2") (pin "12") (pinfunction "12_12") (pintype "passive"))
      (node (ref "U1") (pin "34") (pinfunction "GPIO38/FSPIWP/SUBSPIWP_34") (pintype "passive"))
    )
    (net (code "49") (name "/GPIO39") (class "Default")
      (node (ref "J2") (pin "11") (pinfunction "11_11") (pintype "passive"))
      (node (ref "U1") (pin "35") (pinfunction "MTCK/GPIO39/CLK_OUT3/SUBSPICS1_35") (pintype "passive"))
    )
    (net (code "50") (name "/GPIO40") (class "Default")
      (node (ref "J2") (pin "10") (pinfunction "10_10") (pintype "passive"))
      (node (ref "U1") (pin "36") (pinfunction "MTDO/GPIO40/CLK_OUT2_36") (pintype "passive"))
    )
    (net (code "51") (name "/GPIO41") (class "Default")
      (node (ref "J2") (pin "9") (pinfunction "9_9") (pintype "passive"))
      (node (ref "U1") (pin "37") (pinfunction "MTDI/GPIO41/CLK_OUT1_37") (pintype "passive"))
    )
    (net (code "52") (name "/GPIO42") (class "Default")
      (node (ref "J2") (pin "8") (pinfunction "8_8") (pintype "passive"))
      (node (ref "U1") (pin "38") (pinfunction "MTMS/GPIO42_38") (pintype "passive"))
    )
    (net (code "53") (name "/GPIO45") (class "Default")
      (node (ref "J2") (pin "5") (pinfunction "5_5") (pintype "passive"))
      (node (ref "U1") (pin "41") (pinfunction "GPIO45_41") (pintype "passive"))
    )
    (net (code "54") (name "/GPIO46") (class "Default")
      (node (ref "J2") (pin "4") (pinfunction "4_4") (pintype "passive"))
      (node (ref "U1") (pin "44") (pinfunction "GPIO46_44") (pintype "passive"))
    )
    (net (code "55") (name "/GPIO47") (class "Default")
      (node (ref "J2") (pin "23") (pinfunction "23_23") (pintype "passive"))
      (node (ref "U1") (pin "27") (pinfunction "GPIO47/SPICLK_P_DIFF/SUBSPICLK_P_DIFF_27") (pintype "passive"))
    )
    (net (code "56") (name "/GPIO48") (class "Default")
      (node (ref "J2") (pin "22") (pinfunction "22_22") (pintype "passive"))
      (node (ref "U1") (pin "30") (pinfunction "GPIO48/SPICLK_N_DIFF/SUBSPICLK_N_DIFF_30") (pintype "passive"))
    )
    (net (code "57") (name "/RTS FTDI") (class "Default")
      (node (ref "R17") (pin "1") (pinfunction "1_1") (pintype "passive"))
      (node (ref "T1") (pin "2") (pinfunction "E_2") (pintype "passive"))
      (node (ref "U2") (pin "19") (pinfunction "~{RTS}_19") (pintype "output"))
    )
    (net (code "58") (name "/RXD FTDI") (class "Default")
      (node (ref "R20") (pin "2") (pinfunction "2_2") (pintype "passive"))
      (node (ref "U2") (pin "1") (pinfunction "RXD_1") (pintype "input"))
    )
    (net (code "59") (name "/TXD FTDI") (class "Default")
      (node (ref "R19") (pin "2") (pinfunction "2_2") (pintype "passive"))
      (node (ref "U2") (pin "17") (pinfunction "TXD_17") (pintype "output"))
    )
    (net (code "60") (name "/U0RXD") (class "Default")
      (node (ref "J2") (pin "6") (pinfunction "6_6") (pintype "passive"))
      (node (ref "R20") (pin "1") (pinfunction "1_1") (pintype "passive"))
      (node (ref "U1") (pin "40") (pinfunction "U0RXD/GPIO44/CLK_OUT2_40") (pintype "passive"))
    )
    (net (code "61") (name "/U0TXD") (class "Default")
      (node (ref "J2") (pin "7") (pinfunction "7_7") (pintype "passive"))
      (node (ref "R19") (pin "1") (pinfunction "1_1") (pintype "passive"))
      (node (ref "U1") (pin "39") (pinfunction "U0TXD/GPIO43/CLK_OUT1_39") (pintype "passive"))
    )
    (net (code "62") (name "/VBUS SENSE") (class "Default")
      (node (ref "R13") (pin "2") (pinfunction "2_2") (pintype "passive"))
      (node (ref "R9") (pin "1") (pinfunction "1_1") (pintype "passive"))
      (node (ref "U2") (pin "16") (pinfunction "CBUS3_16") (pintype "passive"))
    )
    (net (code "63") (name "GND") (class "Default")
      (node (ref "C1") (pin "1") (pinfunction "1_1") (pintype "passive"))
      (node (ref "C10") (pin "1") (pinfunction "1_1") (pintype "passive"))
      (node (ref "C11") (pin "1") (pinfunction "1_1") (pintype "passive"))
      (node (ref "C12") (pin "1") (pinfunction "1_1") (pintype "passive"))
      (node (ref "C13") (pin "1") (pinfunction "1_1") (pintype "passive"))
      (node (ref "C14") (pin "1") (pinfunction "1_1") (pintype "passive"))
      (node (ref "C2") (pin "1") (pinfunction "1_1") (pintype "passive"))
      (node (ref "C3") (pin "1") (pinfunction "1_1") (pintype "passive"))
      (node (ref "C4") (pin "1") (pinfunction "1_1") (pintype "passive"))
      (node (ref "C5") (pin "1") (pinfunction "1_1") (pintype "passive"))
      (node (ref "C6") (pin "1") (pinfunction "1_1") (pintype "passive"))
      (node (ref "C7") (pin "1") (pinfunction "1_1") (pintype "passive"))
      (node (ref "C8") (pin "1") (pinfunction "1_1") (pintype "passive"))
      (node (ref "C9") (pin "1") (pinfunction "1_1") (pintype "passive"))
      (node (ref "D1") (pin "1") (pinfunction "1_1") (pintype "passive"))
      (node (ref "J1") (pin "1") (pinfunction "1_1") (pintype "passive"))
      (node (ref "J1") (pin "23") (pinfunction "23_23") (pintype "passive"))
      (node (ref "J10") (pin "1") (pintype "passive"))
      (node (ref "J11") (pin "1") (pintype "passive"))
      (node (ref "J12") (pin "1") (pintype "passive"))
      (node (ref "J2") (pin "2") (pinfunction "2_2") (pintype "passive"))
      (node (ref "J2") (pin "24") (pinfunction "24_24") (pintype "passive"))
      (node (ref "J3") (pin "A1B12") (pinfunction "GND_A1B12_A1B12") (pintype "passive"))
      (node (ref "J3") (pin "B1A12") (pinfunction "GND_B1A12_B1A12") (pintype "passive"))
      (node (ref "J3") (pin "S1") (pinfunction "SHIELD_1_S1") (pintype "passive"))
      (node (ref "J3") (pin "S2") (pinfunction "SHIELD_2_S2") (pintype "passive"))
      (node (ref "J3") (pin "S3") (pinfunction "SHIELD_3_S3") (pintype "passive"))
      (node (ref "J3") (pin "S4") (pinfunction "SHIELD_4_S4") (pintype "passive"))
      (node (ref "J4") (pin "A1B12") (pinfunction "GND_A1B12_A1B12") (pintype "passive"))
      (node (ref "J4") (pin "B1A12") (pinfunction "GND_B1A12_B1A12") (pintype "passive"))
      (node (ref "J4") (pin "S1") (pinfunction "SHIELD_1_S1") (pintype "passive"))
      (node (ref "J4") (pin "S2") (pinfunction "SHIELD_2_S2") (pintype "passive"))
      (node (ref "J4") (pin "S3") (pinfunction "SHIELD_3_S3") (pintype "passive"))
      (node (ref "J4") (pin "S4") (pinfunction "SHIELD_4_S4") (pintype "passive"))
      (node (ref "J5") (pin "1") (pintype "passive"))
      (node (ref "J6") (pin "1") (pintype "passive"))
      (node (ref "J7") (pin "1") (pintype "passive"))
      (node (ref "J9") (pin "2") (pinfunction "GND_2") (pintype "power_in"))
      (node (ref "J9") (pin "4") (pinfunction "GND_4") (pintype "power_in"))
      (node (ref "R10") (pin "1") (pinfunction "1_1") (pintype "passive"))
      (node (ref "R11") (pin "1") (pinfunction "1_1") (pintype "passive"))
      (node (ref "R12") (pin "2") (pinfunction "2_2") (pintype "passive"))
      (node (ref "R13") (pin "1") (pinfunction "1_1") (pintype "passive"))
      (node (ref "R14") (pin "1") (pinfunction "1_1") (pintype "passive"))
      (node (ref "R15") (pin "1") (pinfunction "1_1") (pintype "passive"))
      (node (ref "SW1") (pin "3") (pinfunction "3_3") (pintype "passive"))
      (node (ref "SW1") (pin "4") (pinfunction "4_4") (pintype "passive"))
      (node (ref "SW2") (pin "3") (pinfunction "3_3") (pintype "passive"))
      (node (ref "SW2") (pin "4") (pinfunction "4_4") (pintype "passive"))
      (node (ref "U1") (pin "1") (pinfunction "GND_01_1") (pintype "passive"))
      (node (ref "U1") (pin "2") (pinfunction "GND_02_2") (pintype "passive"))
      (node (ref "U1") (pin "42") (pinfunction "GND_42") (pintype "passive"))
      (node (ref "U1") (pin "43") (pinfunction "GND_43") (pintype "passive"))
      (node (ref "U1") (pin "46") (pinfunction "GND_46_46") (pintype "passive"))
      (node (ref "U1") (pin "47") (pinfunction "GND_47_47") (pintype "passive"))
      (node (ref "U1") (pin "48") (pinfunction "GND_48_48") (pintype "passive"))
      (node (ref "U1") (pin "49") (pinfunction "GND_49_49") (pintype "passive"))
      (node (ref "U1") (pin "50") (pinfunction "GND_50_50") (pintype "passive"))
      (node (ref "U1") (pin "51") (pinfunction "GND_51_51") (pintype "passive"))
      (node (ref "U1") (pin "52") (pinfunction "GND_52_52") (pintype "passive"))
      (node (ref "U1") (pin "53") (pinfunction "GND_53_53") (pintype "passive"))
      (node (ref "U1") (pin "54") (pinfunction "GND_54_54") (pintype "passive"))
      (node (ref "U1") (pin "55") (pinfunction "GND_55_55") (pintype "passive"))
      (node (ref "U1") (pin "56") (pinfunction "GND_56_56") (pintype "passive"))
      (node (ref "U1") (pin "57") (pinfunction "GND_57_57") (pintype "passive"))
      (node (ref "U1") (pin "58") (pinfunction "GND_58_58") (pintype "passive"))
      (node (ref "U1") (pin "59") (pinfunction "GND_59_59") (pintype "passive"))
      (node (ref "U1") (pin "60") (pinfunction "GND_60_60") (pintype "passive"))
      (node (ref "U1") (pin "61") (pinfunction "GND_61_61") (pintype "passive"))
      (node (ref "U1") (pin "62") (pinfunction "GND_62_62") (pintype "passive"))
      (node (ref "U1") (pin "63") (pinfunction "GND_63_63") (pintype "passive"))
      (node (ref "U1") (pin "64") (pinfunction "GND_64_64") (pintype "passive"))
      (node (ref "U1") (pin "65") (pinfunction "GND_65_65") (pintype "passive"))
      (node (ref "U1") (pin "66") (pinfunction "GND_66_66") (pintype "passive"))
      (node (ref "U1") (pin "67") (pinfunction "GND_67_67") (pintype "passive"))
      (node (ref "U1") (pin "68") (pinfunction "GND_68_68") (pintype "passive"))
      (node (ref "U1") (pin "69") (pinfunction "GND_69_69") (pintype "passive"))
      (node (ref "U1") (pin "70") (pinfunction "GND_70_70") (pintype "passive"))
      (node (ref "U1") (pin "71") (pinfunction "GND_71_71") (pintype "passive"))
      (node (ref "U1") (pin "72") (pinfunction "GND_72_72") (pintype "passive"))
      (node (ref "U1") (pin "73") (pinfunction "GND_73_73") (pintype "passive"))
      (node (ref "U2") (pin "13") (pinfunction "GND_13") (pintype "passive"))
      (node (ref "U2") (pin "21") (pinfunction "GND_21") (pintype "passive"))
      (node (ref "U2") (pin "3") (pinfunction "GND_3") (pintype "passive"))
    )
    (net (code "64") (name "Net-(D1-Pad2)") (class "Default")
      (node (ref "D1") (pin "2") (pinfunction "2_2") (pintype "passive"))
      (node (ref "R6") (pin "1") (pinfunction "1_1") (pintype "passive"))
    )
    (net (code "65") (name "Net-(D2-Pad2)") (class "Default")
      (node (ref "D2") (pin "2") (pinfunction "2_2") (pintype "passive"))
      (node (ref "R4") (pin "1") (pinfunction "1_1") (pintype "passive"))
    )
    (net (code "66") (name "Net-(J3-CC1)") (class "Default")
      (node (ref "J3") (pin "A5") (pinfunction "CC1_A5") (pintype "passive"))
      (node (ref "R11") (pin "2") (pinfunction "2_2") (pintype "passive"))
    )
    (net (code "67") (name "Net-(J3-CC2)") (class "Default")
      (node (ref "J3") (pin "B5") (pinfunction "CC2_B5") (pintype "passive"))
      (node (ref "R10") (pin "2") (pinfunction "2_2") (pintype "passive"))
    )
    (net (code "68") (name "Net-(J4-CC1)") (class "Default")
      (node (ref "J4") (pin "A5") (pinfunction "CC1_A5") (pintype "passive"))
      (node (ref "R15") (pin "2") (pinfunction "2_2") (pintype "passive"))
    )
    (net (code "69") (name "Net-(J4-CC2)") (class "Default")
      (node (ref "J4") (pin "B5") (pinfunction "CC2_B5") (pintype "passive"))
      (node (ref "R14") (pin "2") (pinfunction "2_2") (pintype "passive"))
    )
    (net (code "70") (name "Net-(T1-B)") (class "Default")
      (node (ref "R16") (pin "2") (pinfunction "2_2") (pintype "passive"))
      (node (ref "T1") (pin "1") (pinfunction "B_1") (pintype "passive"))
    )
    (net (code "71") (name "Net-(T2-B)") (class "Default")
      (node (ref "R17") (pin "2") (pinfunction "2_2") (pintype "passive"))
      (node (ref "T2") (pin "1") (pinfunction "B_1") (pintype "passive"))
    )
    (net (code "72") (name "Net-(U2-CBUS0)") (class "Default")
      (node (ref "R12") (pin "1") (pinfunction "1_1") (pintype "passive"))
      (node (ref "U2") (pin "15") (pinfunction "CBUS0_15") (pintype "passive"))
    )
    (net (code "73") (name "Net-(U2-~{RESET})") (class "Default")
      (node (ref "R7") (pin "2") (pinfunction "2_2") (pintype "passive"))
      (node (ref "U2") (pin "11") (pinfunction "~{RESET}_11") (pintype "passive"))
    )
    (net (code "74") (name "unconnected-(J1-Pad24)") (class "Default")
      (node (ref "J1") (pin "24") (pinfunction "24_24") (pintype "passive+no_connect"))
    )
    (net (code "75") (name "unconnected-(J3-SBU1-PadA8)") (class "Default")
      (node (ref "J3") (pin "A8") (pinfunction "SBU1_A8") (pintype "passive+no_connect"))
    )
    (net (code "76") (name "unconnected-(J3-SBU2-PadB8)") (class "Default")
      (node (ref "J3") (pin "B8") (pinfunction "SBU2_B8") (pintype "passive+no_connect"))
    )
    (net (code "77") (name "unconnected-(J4-SBU1-PadA8)") (class "Default")
      (node (ref "J4") (pin "A8") (pinfunction "SBU1_A8") (pintype "passive+no_connect"))
    )
    (net (code "78") (name "unconnected-(J4-SBU2-PadB8)") (class "Default")
      (node (ref "J4") (pin "B8") (pinfunction "SBU2_B8") (pintype "passive+no_connect"))
    )
    (net (code "79") (name "unconnected-(U2-CBUS1-Pad14)") (class "Default")
      (node (ref "U2") (pin "14") (pinfunction "CBUS1_14") (pintype "passive+no_connect"))
    )
    (net (code "80") (name "unconnected-(U2-CBUS2-Pad7)") (class "Default")
      (node (ref "U2") (pin "7") (pinfunction "CBUS2_7") (pintype "passive+no_connect"))
    )
    (net (code "81") (name "unconnected-(U2-~{CTS}-Pad6)") (class "Default")
      (node (ref "U2") (pin "6") (pinfunction "~{CTS}_6") (pintype "input+no_connect"))
    )
    (net (code "82") (name "unconnected-(U2-~{DCD}-Pad5)") (class "Default")
      (node (ref "U2") (pin "5") (pinfunction "~{DCD}_5") (pintype "input+no_connect"))
    )
    (net (code "83") (name "unconnected-(U2-~{DSR}-Pad4)") (class "Default")
      (node (ref "U2") (pin "4") (pinfunction "~{DSR}_4") (pintype "input+no_connect"))
    )
    (net (code "84") (name "unconnected-(U2-~{RI}-Pad2)") (class "Default")
      (node (ref "U2") (pin "2") (pinfunction "~{RI}_2") (pintype "input+no_connect"))
    )
  )
)
